# preamp.net
KiCad netlist of a schematic drawn in EAGLE
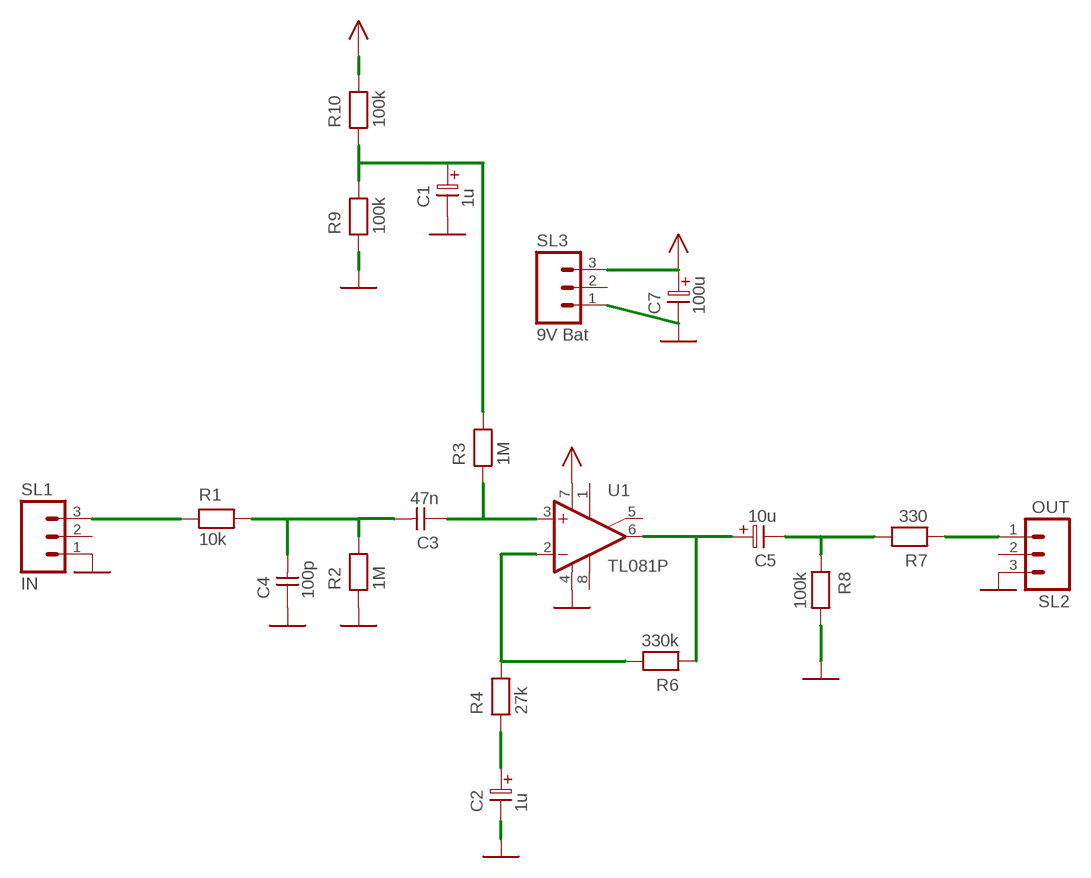
[diagram p0: schematic, sheet 1]

(export (version "E")
  (design (tool "Eeschema 10.0.6"))
  (components
    (comp (ref "C1")
      (value "1u")
      (footprint "eagle-import:ES-2,5L")
      (libsource (lib "eagle-import") (part "ELC-2,5L"))
    )
    (comp (ref "C2")
      (value "1u")
      (footprint "eagle-import:ES-2,5L")
      (libsource (lib "eagle-import") (part "ELC-2,5L"))
    )
    (comp (ref "C3")
      (value "47n")
      (footprint "eagle-import:C-5")
      (libsource (lib "eagle-import") (part "CAPNP-5"))
    )
    (comp (ref "C4")
      (value "100p")
      (footprint "eagle-import:C-5")
      (libsource (lib "eagle-import") (part "CAPNP-5"))
    )
    (comp (ref "C5")
      (value "10u")
      (footprint "eagle-import:ES-2,5L")
      (libsource (lib "eagle-import") (part "ELC-2,5L"))
    )
    (comp (ref "C7")
      (value "100u")
      (footprint "eagle-import:ES-2,5L")
      (libsource (lib "eagle-import") (part "ELC-2,5L"))
    )
    (comp (ref "R1")
      (value "10k")
      (footprint "eagle-import:R-10")
      (libsource (lib "eagle-import") (part "RESEU-10"))
    )
    (comp (ref "R2")
      (value "1M")
      (footprint "eagle-import:R-10")
      (libsource (lib "eagle-import") (part "RESEU-10"))
    )
    (comp (ref "R3")
      (value "1M")
      (footprint "eagle-import:R-10")
      (libsource (lib "eagle-import") (part "RESEU-10"))
    )
    (comp (ref "R4")
      (value "27k")
      (footprint "eagle-import:R-10")
      (libsource (lib "eagle-import") (part "RESEU-10"))
    )
    (comp (ref "R6")
      (value "330k")
      (footprint "eagle-import:R-10")
      (libsource (lib "eagle-import") (part "RESEU-10"))
    )
    (comp (ref "R7")
      (value "330")
      (footprint "eagle-import:R-10")
      (libsource (lib "eagle-import") (part "RESEU-10"))
    )
    (comp (ref "R8")
      (value "100k")
      (footprint "eagle-import:R-10")
      (libsource (lib "eagle-import") (part "RESEU-10"))
    )
    (comp (ref "R9")
      (value "100k")
      (footprint "eagle-import:R-10")
      (libsource (lib "eagle-import") (part "RESEU-10"))
    )
    (comp (ref "R10")
      (value "100k")
      (footprint "eagle-import:R-10")
      (libsource (lib "eagle-import") (part "RESEU-10"))
    )
    (comp (ref "SL1")
      (value "IN")
      (footprint "eagle-import:03P")
      (libsource (lib "eagle-import") (part "M03"))
    )
    (comp (ref "SL2")
      (value "OUT")
      (footprint "eagle-import:03P")
      (libsource (lib "eagle-import") (part "M03"))
    )
    (comp (ref "SL3")
      (value "9V Bat")
      (footprint "eagle-import:03P")
      (libsource (lib "eagle-import") (part "M03"))
    )
    (comp (ref "U1")
      (value "TL081P")
      (footprint "eagle-import:DIL08")
      (libsource (lib "eagle-import") (part "TL081P"))
    )
  )
  (nets
    (net (code "1") (name "GND") (class "Default")
      (node (ref "C1") (pin "2") (pinfunction "2_2") (pintype "passive"))
      (node (ref "C2") (pin "2") (pinfunction "2_2") (pintype "passive"))
      (node (ref "C4") (pin "1") (pinfunction "1_1") (pintype "passive"))
      (node (ref "C7") (pin "2") (pinfunction "2_2") (pintype "passive"))
      (node (ref "R2") (pin "1") (pinfunction "1_1") (pintype "passive"))
      (node (ref "R8") (pin "2") (pinfunction "2_2") (pintype "passive"))
      (node (ref "R9") (pin "1") (pinfunction "1_1") (pintype "passive"))
      (node (ref "SL1") (pin "1") (pinfunction "1_1") (pintype "passive"))
      (node (ref "SL2") (pin "3") (pinfunction "3_3") (pintype "passive"))
      (node (ref "SL3") (pin "1") (pinfunction "1_1") (pintype "passive"))
      (node (ref "U1") (pin "4") (pinfunction "V-_4") (pintype "power_in"))
    )
    (net (code "2") (name "Net-(C1-Pad1)") (class "Default")
      (node (ref "C1") (pin "1") (pinfunction "1_1") (pintype "passive"))
      (node (ref "R10") (pin "1") (pinfunction "1_1") (pintype "passive"))
      (node (ref "R3") (pin "2") (pinfunction "2_2") (pintype "passive"))
      (node (ref "R9") (pin "2") (pinfunction "2_2") (pintype "passive"))
    )
    (net (code "3") (name "Net-(C2-Pad1)") (class "Default")
      (node (ref "C2") (pin "1") (pinfunction "1_1") (pintype "passive"))
      (node (ref "R4") (pin "1") (pinfunction "1_1") (pintype "passive"))
    )
    (net (code "4") (name "Net-(C3-Pad2)") (class "Default")
      (node (ref "C3") (pin "2") (pinfunction "2_2") (pintype "passive"))
      (node (ref "C4") (pin "2") (pinfunction "2_2") (pintype "passive"))
      (node (ref "R1") (pin "2") (pinfunction "2_2") (pintype "passive"))
      (node (ref "R2") (pin "2") (pinfunction "2_2") (pintype "passive"))
    )
    (net (code "5") (name "Net-(C5-Pad2)") (class "Default")
      (node (ref "C5") (pin "2") (pinfunction "2_2") (pintype "passive"))
      (node (ref "R7") (pin "2") (pinfunction "2_2") (pintype "passive"))
      (node (ref "R8") (pin "1") (pinfunction "1_1") (pintype "passive"))
    )
    (net (code "6") (name "Net-(R1-Pad1)") (class "Default")
      (node (ref "R1") (pin "1") (pinfunction "1_1") (pintype "passive"))
      (node (ref "SL1") (pin "3") (pinfunction "3_3") (pintype "passive"))
    )
    (net (code "7") (name "Net-(R7-Pad1)") (class "Default")
      (node (ref "R7") (pin "1") (pinfunction "1_1") (pintype "passive"))
      (node (ref "SL2") (pin "1") (pinfunction "1_1") (pintype "passive"))
    )
    (net (code "8") (name "Net-(U1-+IN)") (class "Default")
      (node (ref "C3") (pin "1") (pinfunction "1_1") (pintype "passive"))
      (node (ref "R3") (pin "1") (pinfunction "1_1") (pintype "passive"))
      (node (ref "U1") (pin "3") (pinfunction "+IN_3") (pintype "input"))
    )
    (net (code "9") (name "Net-(U1--IN)") (class "Default")
      (node (ref "R4") (pin "2") (pinfunction "2_2") (pintype "passive"))
      (node (ref "R6") (pin "2") (pinfunction "2_2") (pintype "passive"))
      (node (ref "U1") (pin "2") (pinfunction "-IN_2") (pintype "input"))
    )
    (net (code "10") (name "Net-(U1-OUT)") (class "Default")
      (node (ref "C5") (pin "1") (pinfunction "1_1") (pintype "passive"))
      (node (ref "R6") (pin "1") (pinfunction "1_1") (pintype "passive"))
      (node (ref "U1") (pin "6") (pinfunction "OUT_6") (pintype "output"))
    )
    (net (code "11") (name "VCC") (class "Default")
      (node (ref "C7") (pin "1") (pinfunction "1_1") (pintype "passive"))
      (node (ref "R10") (pin "2") (pinfunction "2_2") (pintype "passive"))
      (node (ref "SL3") (pin "3") (pinfunction "3_3") (pintype "passive"))
      (node (ref "U1") (pin "7") (pinfunction "V+_7") (pintype "power_in"))
    )
    (net (code "12") (name "unconnected-(SL1-Pad2)") (class "Default")
      (node (ref "SL1") (pin "2") (pinfunction "2_2") (pintype "passive"))
    )
    (net (code "13") (name "unconnected-(SL2-Pad2)") (class "Default")
      (node (ref "SL2") (pin "2") (pinfunction "2_2") (pintype "passive"))
    )
    (net (code "14") (name "unconnected-(SL3-Pad2)") (class "Default")
      (node (ref "SL3") (pin "2") (pinfunction "2_2") (pintype "passive"))
    )
    (net (code "15") (name "unconnected-(U1-ON1-Pad1)") (class "Default")
      (node (ref "U1") (pin "1") (pinfunction "ON1_1") (pintype "passive"))
    )
    (net (code "16") (name "unconnected-(U1-ON2-Pad5)") (class "Default")
      (node (ref "U1") (pin "5") (pinfunction "ON2_5") (pintype "passive"))
    )
    (net (code "17") (name "unconnected-(U1-OPT-Pad8)") (class "Default")
      (node (ref "U1") (pin "8") (pinfunction "OPT_8") (pintype "passive"))
    )
  )
)
